# Control_ESP32.net
KiCad netlist of a schematic drawn in Altium Designer
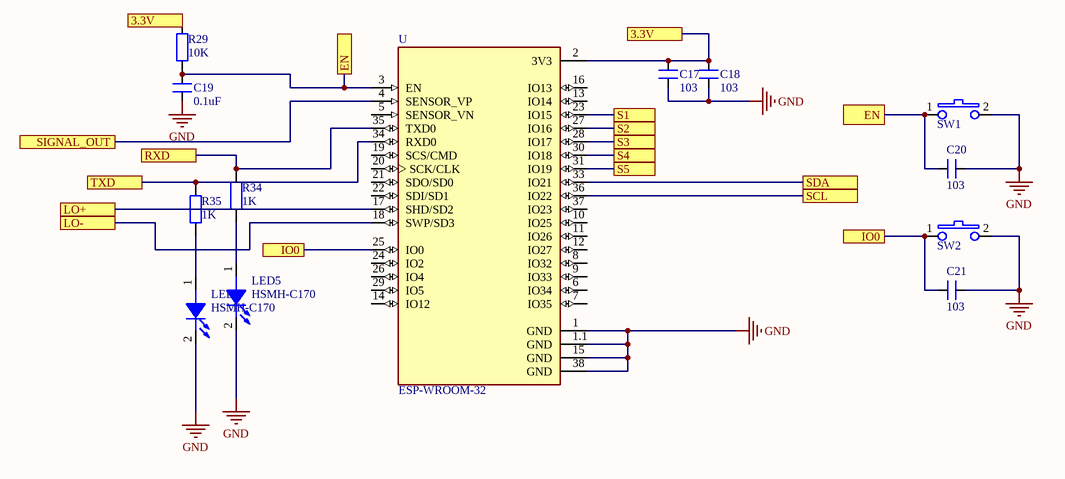
[diagram p0: Control_ESP32.SchDoc]

(export (version "E")
  (design (tool "Eeschema 10.0.6"))
  (components
    (comp (ref "C17")
      (value "103")
      (footprint "SM-0805")
      (description "Cap SMD")
      (libsource (lib "hphonglib") (part "CM"))
    )
    (comp (ref "C18")
      (value "103")
      (footprint "SM-0805")
      (description "Cap SMD")
      (libsource (lib "hphonglib") (part "CM"))
    )
    (comp (ref "C19")
      (value "0.1uF")
      (footprint "SM-0805")
      (description "Cap SMD")
      (libsource (lib "hphonglib") (part "CM"))
    )
    (comp (ref "C20")
      (value "103")
      (footprint "SM-0805")
      (description "Cap SMD")
      (libsource (lib "hphonglib") (part "CM"))
    )
    (comp (ref "C21")
      (value "103")
      (footprint "SM-0805")
      (description "Cap SMD")
      (libsource (lib "hphonglib") (part "CM"))
    )
    (comp (ref "LED5")
      (value "HSMH-C170")
      (footprint "LED.SMD.RED")
      (description "Typical GaAs SMD LED")
      (fields (field (name "MANUFACTURER") "Lite-On Inc") (field (name "PUBLISHER") "Hoang Nguyen"))
      (libsource (lib "hphonglib") (part "LED_1"))
    )
    (comp (ref "LED6")
      (value "HSMH-C170")
      (footprint "LED.SMD.RED")
      (description "Typical GaAs SMD LED")
      (fields (field (name "MANUFACTURER") "Lite-On Inc") (field (name "PUBLISHER") "Hoang Nguyen"))
      (libsource (lib "hphonglib") (part "LED_1"))
    )
    (comp (ref "R29")
      (value "10K")
      (footprint "DIEN TRO 0805")
      (description "RES_0805")
      (fields (field (name "Comment") "RES_SMD_0805") (field (name "PUBLISHER") "Altium Limited"))
      (libsource (lib "hphonglib") (part "RES_SMD_0805"))
    )
    (comp (ref "R34")
      (value "1K")
      (footprint "DIEN TRO 0805")
      (description "RES_0805")
      (fields (field (name "Comment") "RES_SMD_0805") (field (name "PUBLISHER") "Altium Limited"))
      (libsource (lib "") (part "RES_SMD_0805_1"))
    )
    (comp (ref "R35")
      (value "1K")
      (footprint "DIEN TRO 0805")
      (description "RES_0805")
      (fields (field (name "Comment") "RES_SMD_0805") (field (name "PUBLISHER") "Altium Limited"))
      (libsource (lib "") (part "RES_SMD_0805_1"))
    )
    (comp (ref "SW1")
      (value "PTS635")
      (footprint "TactSwitches.PTS635.SMT")
      (description "SWITCH TACT MOM SPST SMD")
      (fields (field (name "MANUFACTURER") "C&K Components") (field (name "PUBLISHER") "Hoang Nguyen"))
      (libsource (lib "hphonglib") (part "SW TACT MOM SPST"))
    )
    (comp (ref "SW2")
      (value "PTS635")
      (footprint "TactSwitches.PTS635.SMT")
      (description "SWITCH TACT MOM SPST SMD")
      (fields (field (name "MANUFACTURER") "C&K Components") (field (name "PUBLISHER") "Hoang Nguyen"))
      (libsource (lib "hphonglib") (part "SW TACT MOM SPST"))
    )
    (comp (ref "U")
      (value "ESP-WROOM-32")
      (footprint "MODULE_ESP-WROOM-32")
      (description "WiFi 802.11b/g/n/d/e/i Transceiver Module 2.4GHz Surface Mount")
      (fields (field (name "MF") "Olimex LTD"))
      (libsource (lib "EMG_IoT_V2.0") (part "ESP-WROOM-32"))
    )
  )
  (nets
    (net (code "1") (name "/3.3V") (class "Default")
      (node (ref "C17") (pin "1") (pinfunction "1_1") (pintype "passive"))
      (node (ref "C18") (pin "1") (pinfunction "1_1") (pintype "passive"))
      (node (ref "R29") (pin "2") (pinfunction "2_2") (pintype "passive"))
      (node (ref "U") (pin "2") (pinfunction "3V3_2") (pintype "power_in"))
    )
    (net (code "2") (name "/EN") (class "Default")
      (node (ref "C19") (pin "1") (pinfunction "1_1") (pintype "passive"))
      (node (ref "C20") (pin "1") (pinfunction "1_1") (pintype "passive"))
      (node (ref "R29") (pin "1") (pinfunction "1_1") (pintype "passive"))
      (node (ref "SW1") (pin "1") (pinfunction "1_1") (pintype "passive"))
      (node (ref "U") (pin "3") (pinfunction "EN_3") (pintype "input"))
    )
    (net (code "3") (name "/IO0") (class "Default")
      (node (ref "C21") (pin "1") (pinfunction "1_1") (pintype "passive"))
      (node (ref "SW2") (pin "1") (pinfunction "1_1") (pintype "passive"))
      (node (ref "U") (pin "25") (pinfunction "IO0_25") (pintype "bidirectional"))
    )
    (net (code "4") (name "/LO+") (class "Default")
      (node (ref "U") (pin "17") (pinfunction "SHD/SD2_17") (pintype "bidirectional"))
    )
    (net (code "5") (name "/LO-") (class "Default")
      (node (ref "U") (pin "18") (pinfunction "SWP/SD3_18") (pintype "bidirectional"))
    )
    (net (code "6") (name "/RXD") (class "Default")
      (node (ref "R34") (pin "1") (pinfunction "1_1") (pintype "passive"))
      (node (ref "U") (pin "35") (pinfunction "TXD0_35") (pintype "bidirectional"))
    )
    (net (code "7") (name "/S1") (class "Default")
      (node (ref "U") (pin "23") (pinfunction "IO15_23") (pintype "bidirectional"))
    )
    (net (code "8") (name "/S2") (class "Default")
      (node (ref "U") (pin "27") (pinfunction "IO16_27") (pintype "bidirectional"))
    )
    (net (code "9") (name "/S3") (class "Default")
      (node (ref "U") (pin "28") (pinfunction "IO17_28") (pintype "bidirectional"))
    )
    (net (code "10") (name "/S4") (class "Default")
      (node (ref "U") (pin "30") (pinfunction "IO18_30") (pintype "bidirectional"))
    )
    (net (code "11") (name "/S5") (class "Default")
      (node (ref "U") (pin "31") (pinfunction "IO19_31") (pintype "bidirectional"))
    )
    (net (code "12") (name "/SCL") (class "Default")
      (node (ref "U") (pin "36") (pinfunction "IO22_36") (pintype "bidirectional"))
    )
    (net (code "13") (name "/SDA") (class "Default")
      (node (ref "U") (pin "33") (pinfunction "IO21_33") (pintype "bidirectional"))
    )
    (net (code "14") (name "/SIGNAL_OUT") (class "Default")
      (node (ref "U") (pin "4") (pinfunction "SENSOR_VP_4") (pintype "input"))
    )
    (net (code "15") (name "/TXD") (class "Default")
      (node (ref "R35") (pin "1") (pinfunction "1_1") (pintype "passive"))
      (node (ref "U") (pin "34") (pinfunction "RXD0_34") (pintype "bidirectional"))
    )
    (net (code "16") (name "GND") (class "Default")
      (node (ref "C17") (pin "2") (pinfunction "2_2") (pintype "passive"))
      (node (ref "C18") (pin "2") (pinfunction "2_2") (pintype "passive"))
      (node (ref "C19") (pin "2") (pinfunction "2_2") (pintype "passive"))
      (node (ref "C20") (pin "2") (pinfunction "2_2") (pintype "passive"))
      (node (ref "C21") (pin "2") (pinfunction "2_2") (pintype "passive"))
      (node (ref "LED5") (pin "2") (pinfunction "K_2") (pintype "passive"))
      (node (ref "LED6") (pin "2") (pinfunction "K_2") (pintype "passive"))
      (node (ref "SW1") (pin "2") (pinfunction "2_2") (pintype "passive"))
      (node (ref "SW2") (pin "2") (pinfunction "2_2") (pintype "passive"))
      (node (ref "U") (pin "1") (pinfunction "GND_1") (pintype "power_in"))
      (node (ref "U") (pin "1.1") (pinfunction "GND_1.1") (pintype "power_in"))
      (node (ref "U") (pin "15") (pinfunction "GND_15") (pintype "power_in"))
      (node (ref "U") (pin "38") (pinfunction "GND_38") (pintype "power_in"))
    )
    (net (code "17") (name "Net-(LED5-A)") (class "Default")
      (node (ref "LED5") (pin "1") (pinfunction "A_1") (pintype "passive"))
      (node (ref "R34") (pin "2") (pinfunction "2_2") (pintype "passive"))
    )
    (net (code "18") (name "Net-(LED6-A)") (class "Default")
      (node (ref "LED6") (pin "1") (pinfunction "A_1") (pintype "passive"))
      (node (ref "R35") (pin "2") (pinfunction "2_2") (pintype "passive"))
    )
    (net (code "19") (name "unconnected-(U-IO2-Pad24)") (class "Default")
      (node (ref "U") (pin "24") (pinfunction "IO2_24") (pintype "bidirectional"))
    )
    (net (code "20") (name "unconnected-(U-IO4-Pad26)") (class "Default")
      (node (ref "U") (pin "26") (pinfunction "IO4_26") (pintype "bidirectional"))
    )
    (net (code "21") (name "unconnected-(U-IO5-Pad29)") (class "Default")
      (node (ref "U") (pin "29") (pinfunction "IO5_29") (pintype "bidirectional"))
    )
    (net (code "22") (name "unconnected-(U-IO12-Pad14)") (class "Default")
      (node (ref "U") (pin "14") (pinfunction "IO12_14") (pintype "bidirectional"))
    )
    (net (code "23") (name "unconnected-(U-IO13-Pad16)") (class "Default")
      (node (ref "U") (pin "16") (pinfunction "IO13_16") (pintype "bidirectional"))
    )
    (net (code "24") (name "unconnected-(U-IO14-Pad13)") (class "Default")
      (node (ref "U") (pin "13") (pinfunction "IO14_13") (pintype "bidirectional"))
    )
    (net (code "25") (name "unconnected-(U-IO23-Pad37)") (class "Default")
      (node (ref "U") (pin "37") (pinfunction "IO23_37") (pintype "bidirectional"))
    )
    (net (code "26") (name "unconnected-(U-IO25-Pad10)") (class "Default")
      (node (ref "U") (pin "10") (pinfunction "IO25_10") (pintype "bidirectional"))
    )
    (net (code "27") (name "unconnected-(U-IO26-Pad11)") (class "Default")
      (node (ref "U") (pin "11") (pinfunction "IO26_11") (pintype "bidirectional"))
    )
    (net (code "28") (name "unconnected-(U-IO27-Pad12)") (class "Default")
      (node (ref "U") (pin "12") (pinfunction "IO27_12") (pintype "bidirectional"))
    )
    (net (code "29") (name "unconnected-(U-IO32-Pad8)") (class "Default")
      (node (ref "U") (pin "8") (pinfunction "IO32_8") (pintype "bidirectional"))
    )
    (net (code "30") (name "unconnected-(U-IO33-Pad9)") (class "Default")
      (node (ref "U") (pin "9") (pinfunction "IO33_9") (pintype "bidirectional"))
    )
    (net (code "31") (name "unconnected-(U-IO34-Pad6)") (class "Default")
      (node (ref "U") (pin "6") (pinfunction "IO34_6") (pintype "bidirectional"))
    )
    (net (code "32") (name "unconnected-(U-IO35-Pad7)") (class "Default")
      (node (ref "U") (pin "7") (pinfunction "IO35_7") (pintype "bidirectional"))
    )
    (net (code "33") (name "unconnected-(U-SCK{slash}CLK-Pad20)") (class "Default")
      (node (ref "U") (pin "20") (pinfunction "SCK/CLK_20") (pintype "bidirectional"))
    )
    (net (code "34") (name "unconnected-(U-SCS{slash}CMD-Pad19)") (class "Default")
      (node (ref "U") (pin "19") (pinfunction "SCS/CMD_19") (pintype "bidirectional"))
    )
    (net (code "35") (name "unconnected-(U-SDI{slash}SD1-Pad22)") (class "Default")
      (node (ref "U") (pin "22") (pinfunction "SDI/SD1_22") (pintype "bidirectional"))
    )
    (net (code "36") (name "unconnected-(U-SDO{slash}SD0-Pad21)") (class "Default")
      (node (ref "U") (pin "21") (pinfunction "SDO/SD0_21") (pintype "bidirectional"))
    )
    (net (code "37") (name "unconnected-(U-SENSOR_VN-Pad5)") (class "Default")
      (node (ref "U") (pin "5") (pinfunction "SENSOR_VN_5") (pintype "input"))
    )
  )
)
